# RC_Car_Final_Seven.net
KiCad netlist of a schematic drawn in EAGLE
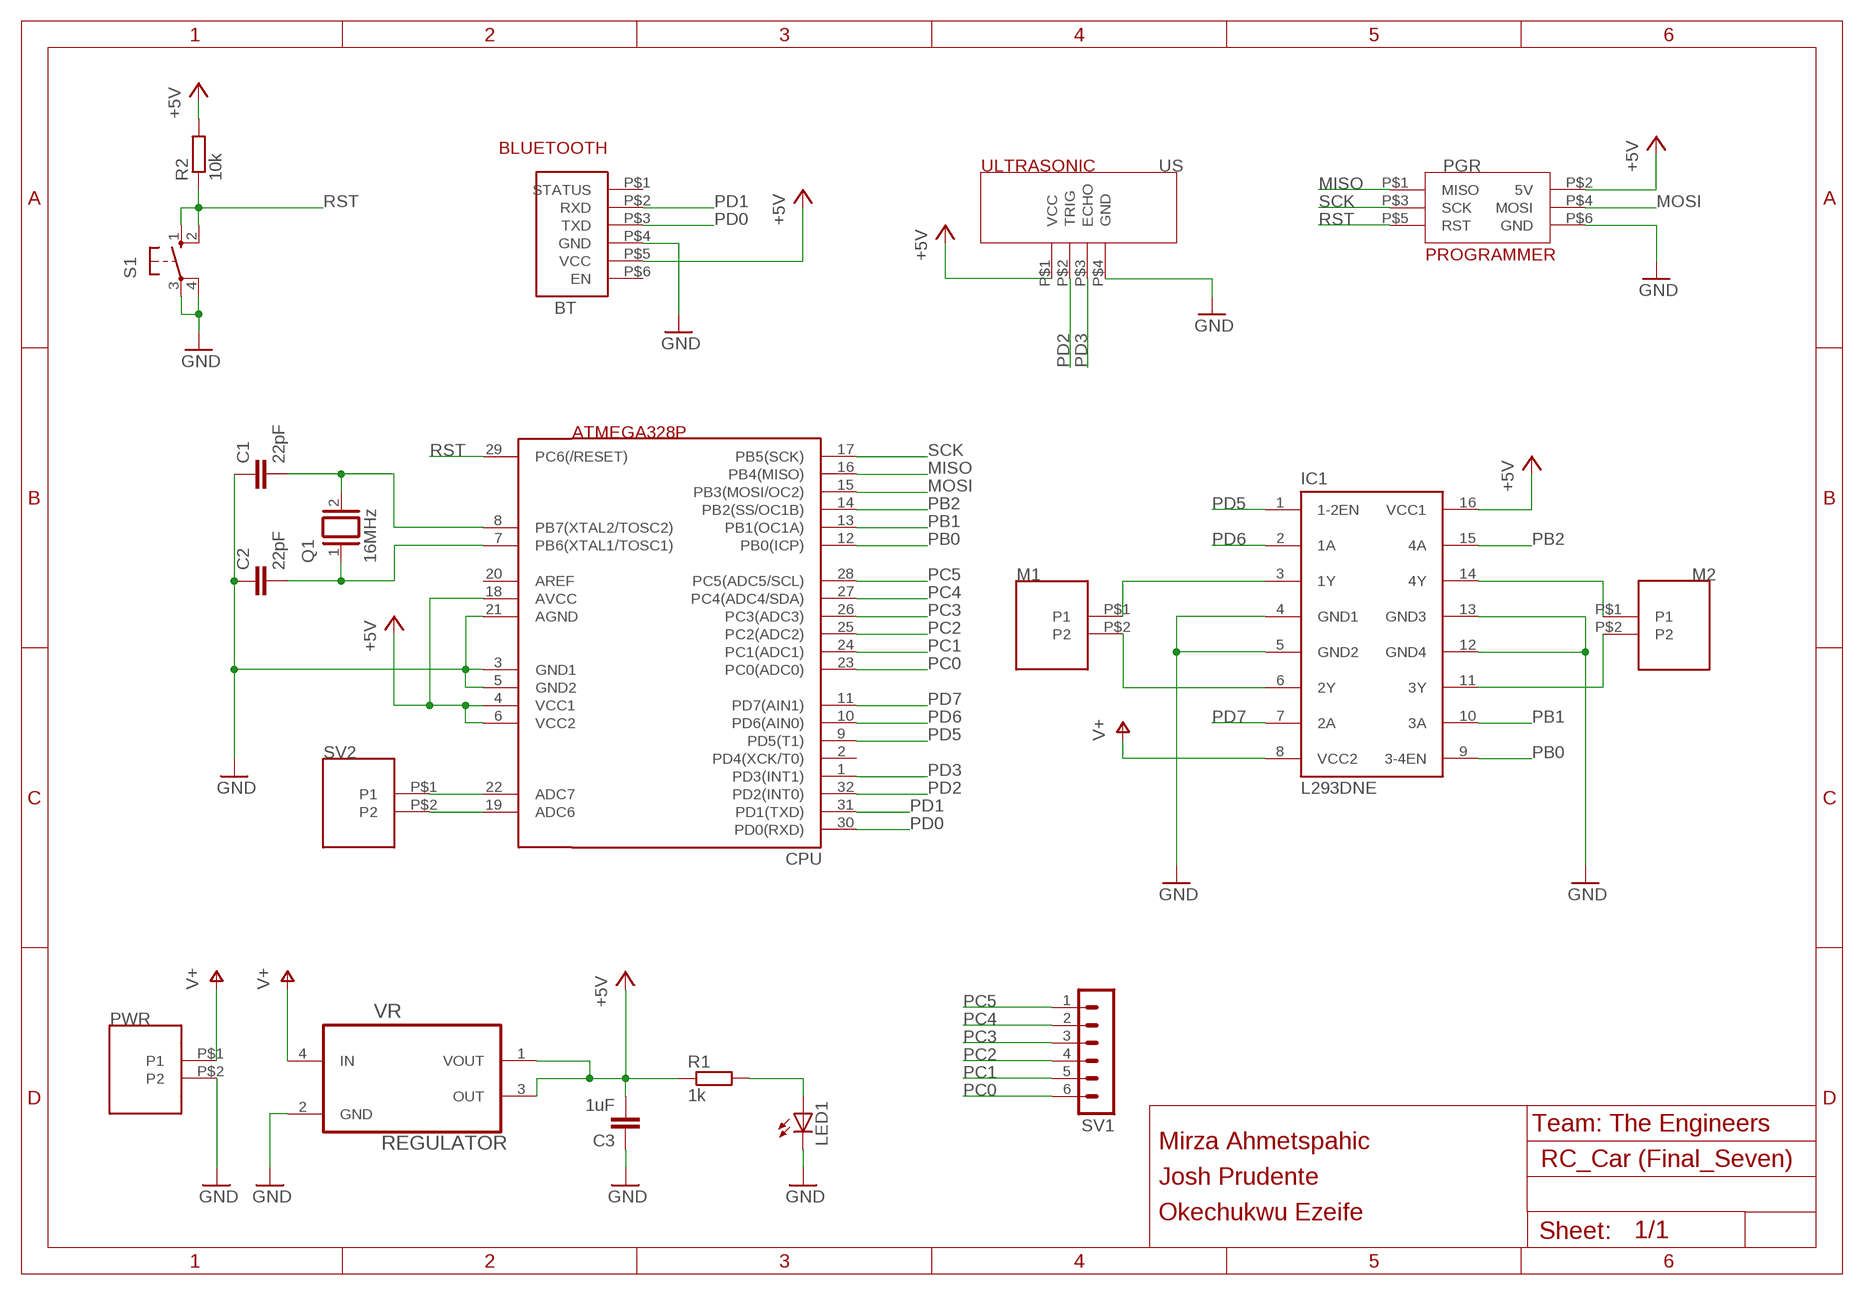
[diagram p0: schematic, sheet 1]

(export (version "E")
  (design (tool "Eeschema 10.0.6"))
  (components
    (comp (ref "BT")
      (value "BLUETOOTH")
      (footprint "eagle-import:BLUETOOTH")
      (libsource (lib "eagle-import") (part "BLUETOOTH"))
    )
    (comp (ref "C1")
      (value "22pF")
      (footprint "eagle-import:C025-030X050")
      (libsource (lib "eagle-import") (part "C2.5P"))
    )
    (comp (ref "C2")
      (value "22pF")
      (footprint "eagle-import:C025-030X050")
      (libsource (lib "eagle-import") (part "C2.5P"))
    )
    (comp (ref "C3")
      (value "1uF")
      (footprint "eagle-import:C025-030X050")
      (libsource (lib "eagle-import") (part "C2.5P"))
    )
    (comp (ref "CPU")
      (value "ATMEGA328P")
      (footprint "eagle-import:ATMEGA328P")
      (libsource (lib "eagle-import") (part "ATMEGA328P"))
    )
    (comp (ref "IC1")
      (value "L293DNE")
      (footprint "eagle-import:L293DNE")
      (fields (field (name "MF") "Texas Instruments"))
      (libsource (lib "eagle-import") (part "L293DNE"))
    )
    (comp (ref "LED1")
      (value "LED3MM")
      (footprint "eagle-import:HLMP-D105")
      (libsource (lib "eagle-import") (part "LED3MM"))
    )
    (comp (ref "M1")
      (value "HEADER")
      (footprint "eagle-import:HEADER")
      (libsource (lib "eagle-import") (part "HEADER"))
    )
    (comp (ref "M2")
      (value "HEADER")
      (footprint "eagle-import:HEADER")
      (libsource (lib "eagle-import") (part "HEADER"))
    )
    (comp (ref "PGR")
      (value "AVR6AVR6")
      (footprint "eagle-import:AVR6")
      (libsource (lib "eagle-import") (part "AVR6AVR6"))
    )
    (comp (ref "PWR")
      (value "HEADER")
      (footprint "eagle-import:HEADER")
      (libsource (lib "eagle-import") (part "HEADER"))
    )
    (comp (ref "Q1")
      (value "16MHz")
      (footprint "eagle-import:QS")
      (libsource (lib "eagle-import") (part "XTAL/S"))
    )
    (comp (ref "R1")
      (value "1k")
      (footprint "eagle-import:0207_10")
      (libsource (lib "eagle-import") (part "R"))
    )
    (comp (ref "R2")
      (value "10k")
      (footprint "eagle-import:0207_10")
      (libsource (lib "eagle-import") (part "R"))
    )
    (comp (ref "S1")
      (value "10-XX")
      (footprint "eagle-import:B3F-10XX")
      (fields (field (name "MPN") "B3F-1000"))
      (libsource (lib "eagle-import") (part "10-XX"))
    )
    (comp (ref "SV1")
      (value "MA06-1")
      (footprint "eagle-import:MA06-1")
      (libsource (lib "eagle-import") (part "MA06-1"))
    )
    (comp (ref "SV2")
      (value "HEADER")
      (footprint "eagle-import:HEADER")
      (libsource (lib "eagle-import") (part "HEADER"))
    )
    (comp (ref "US")
      (value "ULTRASONIC")
      (footprint "eagle-import:ULTRASONIC")
      (libsource (lib "eagle-import") (part "ULTRASONIC"))
    )
    (comp (ref "VR")
      (value "REGULATOR")
      (footprint "eagle-import:REGULATOR")
      (libsource (lib "eagle-import") (part "REGULATOR"))
    )
  )
  (nets
    (net (code "1") (name "+5V") (class "Default")
      (node (ref "BT") (pin "P$5") (pinfunction "VCC_P$5") (pintype "bidirectional"))
      (node (ref "C3") (pin "2") (pinfunction "2_2") (pintype "passive"))
      (node (ref "CPU") (pin "18") (pinfunction "AVCC_18") (pintype "bidirectional"))
      (node (ref "CPU") (pin "4") (pinfunction "VCC1_4") (pintype "bidirectional"))
      (node (ref "CPU") (pin "6") (pinfunction "VCC2_6") (pintype "bidirectional"))
      (node (ref "IC1") (pin "16") (pinfunction "VCC1_16") (pintype "power_in"))
      (node (ref "PGR") (pin "P$2") (pinfunction "5V_P$2") (pintype "bidirectional"))
      (node (ref "R1") (pin "1") (pinfunction "1_1") (pintype "passive"))
      (node (ref "R2") (pin "2") (pinfunction "2_2") (pintype "passive"))
      (node (ref "US") (pin "P$1") (pinfunction "VCC_P$1") (pintype "bidirectional"))
      (node (ref "VR") (pin "1") (pinfunction "VOUT_1") (pintype "bidirectional"))
      (node (ref "VR") (pin "3") (pinfunction "OUT_3") (pintype "bidirectional"))
    )
    (net (code "2") (name "/MISO") (class "Default")
      (node (ref "CPU") (pin "16") (pinfunction "PB4(MISO)_16") (pintype "bidirectional"))
      (node (ref "PGR") (pin "P$1") (pinfunction "MISO_P$1") (pintype "bidirectional"))
    )
    (net (code "3") (name "/MOSI") (class "Default")
      (node (ref "CPU") (pin "15") (pinfunction "PB3(MOSI/OC2)_15") (pintype "bidirectional"))
      (node (ref "PGR") (pin "P$4") (pinfunction "MOSI_P$4") (pintype "bidirectional"))
    )
    (net (code "4") (name "/PB0") (class "Default")
      (node (ref "CPU") (pin "12") (pinfunction "PB0(ICP)_12") (pintype "bidirectional"))
      (node (ref "IC1") (pin "9") (pinfunction "3-4EN_9") (pintype "input"))
    )
    (net (code "5") (name "/PB1") (class "Default")
      (node (ref "CPU") (pin "13") (pinfunction "PB1(OC1A)_13") (pintype "bidirectional"))
      (node (ref "IC1") (pin "10") (pinfunction "3A_10") (pintype "input"))
    )
    (net (code "6") (name "/PB2") (class "Default")
      (node (ref "CPU") (pin "14") (pinfunction "PB2(SS/OC1B)_14") (pintype "bidirectional"))
      (node (ref "IC1") (pin "15") (pinfunction "4A_15") (pintype "input"))
    )
    (net (code "7") (name "/PC0") (class "Default")
      (node (ref "CPU") (pin "23") (pinfunction "PC0(ADC0)_23") (pintype "bidirectional"))
      (node (ref "SV1") (pin "6") (pinfunction "6_6") (pintype "passive"))
    )
    (net (code "8") (name "/PC1") (class "Default")
      (node (ref "CPU") (pin "24") (pinfunction "PC1(ADC1)_24") (pintype "bidirectional"))
      (node (ref "SV1") (pin "5") (pinfunction "5_5") (pintype "passive"))
    )
    (net (code "9") (name "/PC2") (class "Default")
      (node (ref "CPU") (pin "25") (pinfunction "PC2(ADC2)_25") (pintype "bidirectional"))
      (node (ref "SV1") (pin "4") (pinfunction "4_4") (pintype "passive"))
    )
    (net (code "10") (name "/PC3") (class "Default")
      (node (ref "CPU") (pin "26") (pinfunction "PC3(ADC3)_26") (pintype "bidirectional"))
      (node (ref "SV1") (pin "3") (pinfunction "3_3") (pintype "passive"))
    )
    (net (code "11") (name "/PC4") (class "Default")
      (node (ref "CPU") (pin "27") (pinfunction "PC4(ADC4/SDA)_27") (pintype "bidirectional"))
      (node (ref "SV1") (pin "2") (pinfunction "2_2") (pintype "passive"))
    )
    (net (code "12") (name "/PC5") (class "Default")
      (node (ref "CPU") (pin "28") (pinfunction "PC5(ADC5/SCL)_28") (pintype "bidirectional"))
      (node (ref "SV1") (pin "1") (pinfunction "1_1") (pintype "passive"))
    )
    (net (code "13") (name "/PD0") (class "Default")
      (node (ref "BT") (pin "P$3") (pinfunction "TXD_P$3") (pintype "bidirectional"))
      (node (ref "CPU") (pin "30") (pinfunction "PD0(RXD)_30") (pintype "bidirectional"))
    )
    (net (code "14") (name "/PD1") (class "Default")
      (node (ref "BT") (pin "P$2") (pinfunction "RXD_P$2") (pintype "bidirectional"))
      (node (ref "CPU") (pin "31") (pinfunction "PD1(TXD)_31") (pintype "bidirectional"))
    )
    (net (code "15") (name "/PD2") (class "Default")
      (node (ref "CPU") (pin "32") (pinfunction "PD2(INT0)_32") (pintype "bidirectional"))
      (node (ref "US") (pin "P$2") (pinfunction "TRIG_P$2") (pintype "bidirectional"))
    )
    (net (code "16") (name "/PD3") (class "Default")
      (node (ref "CPU") (pin "1") (pinfunction "PD3(INT1)_1") (pintype "bidirectional"))
      (node (ref "US") (pin "P$3") (pinfunction "ECHO_P$3") (pintype "bidirectional"))
    )
    (net (code "17") (name "/PD5") (class "Default")
      (node (ref "CPU") (pin "9") (pinfunction "PD5(T1)_9") (pintype "bidirectional"))
      (node (ref "IC1") (pin "1") (pinfunction "1-2EN_1") (pintype "input"))
    )
    (net (code "18") (name "/PD6") (class "Default")
      (node (ref "CPU") (pin "10") (pinfunction "PD6(AIN0)_10") (pintype "bidirectional"))
      (node (ref "IC1") (pin "2") (pinfunction "1A_2") (pintype "input"))
    )
    (net (code "19") (name "/PD7") (class "Default")
      (node (ref "CPU") (pin "11") (pinfunction "PD7(AIN1)_11") (pintype "bidirectional"))
      (node (ref "IC1") (pin "7") (pinfunction "2A_7") (pintype "input"))
    )
    (net (code "20") (name "/RST") (class "Default")
      (node (ref "CPU") (pin "29") (pinfunction "PC6(/RESET)_29") (pintype "bidirectional"))
      (node (ref "PGR") (pin "P$5") (pinfunction "RST_P$5") (pintype "bidirectional"))
      (node (ref "R2") (pin "1") (pinfunction "1_1") (pintype "passive"))
      (node (ref "S1") (pin "1") (pinfunction "S_1") (pintype "passive"))
      (node (ref "S1") (pin "2") (pinfunction "S1_2") (pintype "passive"))
    )
    (net (code "21") (name "/SCK") (class "Default")
      (node (ref "CPU") (pin "17") (pinfunction "PB5(SCK)_17") (pintype "bidirectional"))
      (node (ref "PGR") (pin "P$3") (pinfunction "SCK_P$3") (pintype "bidirectional"))
    )
    (net (code "22") (name "GND") (class "Default")
      (node (ref "BT") (pin "P$4") (pinfunction "GND_P$4") (pintype "bidirectional"))
      (node (ref "C1") (pin "1") (pinfunction "1_1") (pintype "passive"))
      (node (ref "C2") (pin "1") (pinfunction "1_1") (pintype "passive"))
      (node (ref "C3") (pin "1") (pinfunction "1_1") (pintype "passive"))
      (node (ref "CPU") (pin "21") (pinfunction "AGND_21") (pintype "bidirectional"))
      (node (ref "CPU") (pin "3") (pinfunction "GND1_3") (pintype "bidirectional"))
      (node (ref "CPU") (pin "5") (pinfunction "GND2_5") (pintype "bidirectional"))
      (node (ref "IC1") (pin "12") (pinfunction "GND4_12") (pintype "passive"))
      (node (ref "IC1") (pin "13") (pinfunction "GND3_13") (pintype "passive"))
      (node (ref "IC1") (pin "4") (pinfunction "GND1_4") (pintype "passive"))
      (node (ref "IC1") (pin "5") (pinfunction "GND2_5") (pintype "passive"))
      (node (ref "LED1") (pin "K") (pinfunction "C_K") (pintype "passive"))
      (node (ref "PGR") (pin "P$6") (pinfunction "GND_P$6") (pintype "bidirectional"))
      (node (ref "PWR") (pin "P$2") (pinfunction "P2_P$2") (pintype "bidirectional"))
      (node (ref "S1") (pin "3") (pinfunction "P_3") (pintype "passive"))
      (node (ref "S1") (pin "4") (pinfunction "P1_4") (pintype "passive"))
      (node (ref "US") (pin "P$4") (pinfunction "GND_P$4") (pintype "bidirectional"))
      (node (ref "VR") (pin "2") (pinfunction "GND_2") (pintype "bidirectional"))
    )
    (net (code "23") (name "Net-(CPU-ADC6)") (class "Default")
      (node (ref "CPU") (pin "19") (pinfunction "ADC6_19") (pintype "bidirectional"))
      (node (ref "SV2") (pin "P$2") (pinfunction "P2_P$2") (pintype "bidirectional"))
    )
    (net (code "24") (name "Net-(CPU-ADC7)") (class "Default")
      (node (ref "CPU") (pin "22") (pinfunction "ADC7_22") (pintype "bidirectional"))
      (node (ref "SV2") (pin "P$1") (pinfunction "P1_P$1") (pintype "bidirectional"))
    )
    (net (code "25") (name "Net-(CPU-PB6(XTAL1{slash}TOSC1))") (class "Default")
      (node (ref "C2") (pin "2") (pinfunction "2_2") (pintype "passive"))
      (node (ref "CPU") (pin "7") (pinfunction "PB6(XTAL1/TOSC1)_7") (pintype "bidirectional"))
      (node (ref "Q1") (pin "1") (pinfunction "1_1") (pintype "passive"))
    )
    (net (code "26") (name "Net-(CPU-PB7(XTAL2{slash}TOSC2))") (class "Default")
      (node (ref "C1") (pin "2") (pinfunction "2_2") (pintype "passive"))
      (node (ref "CPU") (pin "8") (pinfunction "PB7(XTAL2/TOSC2)_8") (pintype "bidirectional"))
      (node (ref "Q1") (pin "2") (pinfunction "2_2") (pintype "passive"))
    )
    (net (code "27") (name "Net-(IC1-1Y)") (class "Default")
      (node (ref "IC1") (pin "3") (pinfunction "1Y_3") (pintype "output"))
      (node (ref "M1") (pin "P$1") (pinfunction "P1_P$1") (pintype "bidirectional"))
    )
    (net (code "28") (name "Net-(IC1-2Y)") (class "Default")
      (node (ref "IC1") (pin "6") (pinfunction "2Y_6") (pintype "output"))
      (node (ref "M1") (pin "P$2") (pinfunction "P2_P$2") (pintype "bidirectional"))
    )
    (net (code "29") (name "Net-(IC1-3Y)") (class "Default")
      (node (ref "IC1") (pin "11") (pinfunction "3Y_11") (pintype "output"))
      (node (ref "M2") (pin "P$2") (pinfunction "P2_P$2") (pintype "bidirectional"))
    )
    (net (code "30") (name "Net-(IC1-4Y)") (class "Default")
      (node (ref "IC1") (pin "14") (pinfunction "4Y_14") (pintype "output"))
      (node (ref "M2") (pin "P$1") (pinfunction "P1_P$1") (pintype "bidirectional"))
    )
    (net (code "31") (name "Net-(LED1-PadA)") (class "Default")
      (node (ref "LED1") (pin "A") (pinfunction "A_A") (pintype "passive"))
      (node (ref "R1") (pin "2") (pinfunction "2_2") (pintype "passive"))
    )
    (net (code "32") (name "V+") (class "Default")
      (node (ref "IC1") (pin "8") (pinfunction "VCC2_8") (pintype "power_in"))
      (node (ref "PWR") (pin "P$1") (pinfunction "P1_P$1") (pintype "bidirectional"))
      (node (ref "VR") (pin "4") (pinfunction "IN_4") (pintype "bidirectional"))
    )
    (net (code "33") (name "unconnected-(BT-EN-PadP$6)") (class "Default")
      (node (ref "BT") (pin "P$6") (pinfunction "EN_P$6") (pintype "bidirectional"))
    )
    (net (code "34") (name "unconnected-(BT-STATUS-PadP$1)") (class "Default")
      (node (ref "BT") (pin "P$1") (pinfunction "STATUS_P$1") (pintype "bidirectional"))
    )
    (net (code "35") (name "unconnected-(CPU-AREF-Pad20)") (class "Default")
      (node (ref "CPU") (pin "20") (pinfunction "AREF_20") (pintype "bidirectional"))
    )
    (net (code "36") (name "unconnected-(CPU-PD4(XCK{slash}T0)-Pad2)") (class "Default")
      (node (ref "CPU") (pin "2") (pinfunction "PD4(XCK/T0)_2") (pintype "bidirectional"))
    )
  )
)
